# WSN_v1.net
KiCad netlist of a schematic drawn in Altium Designer
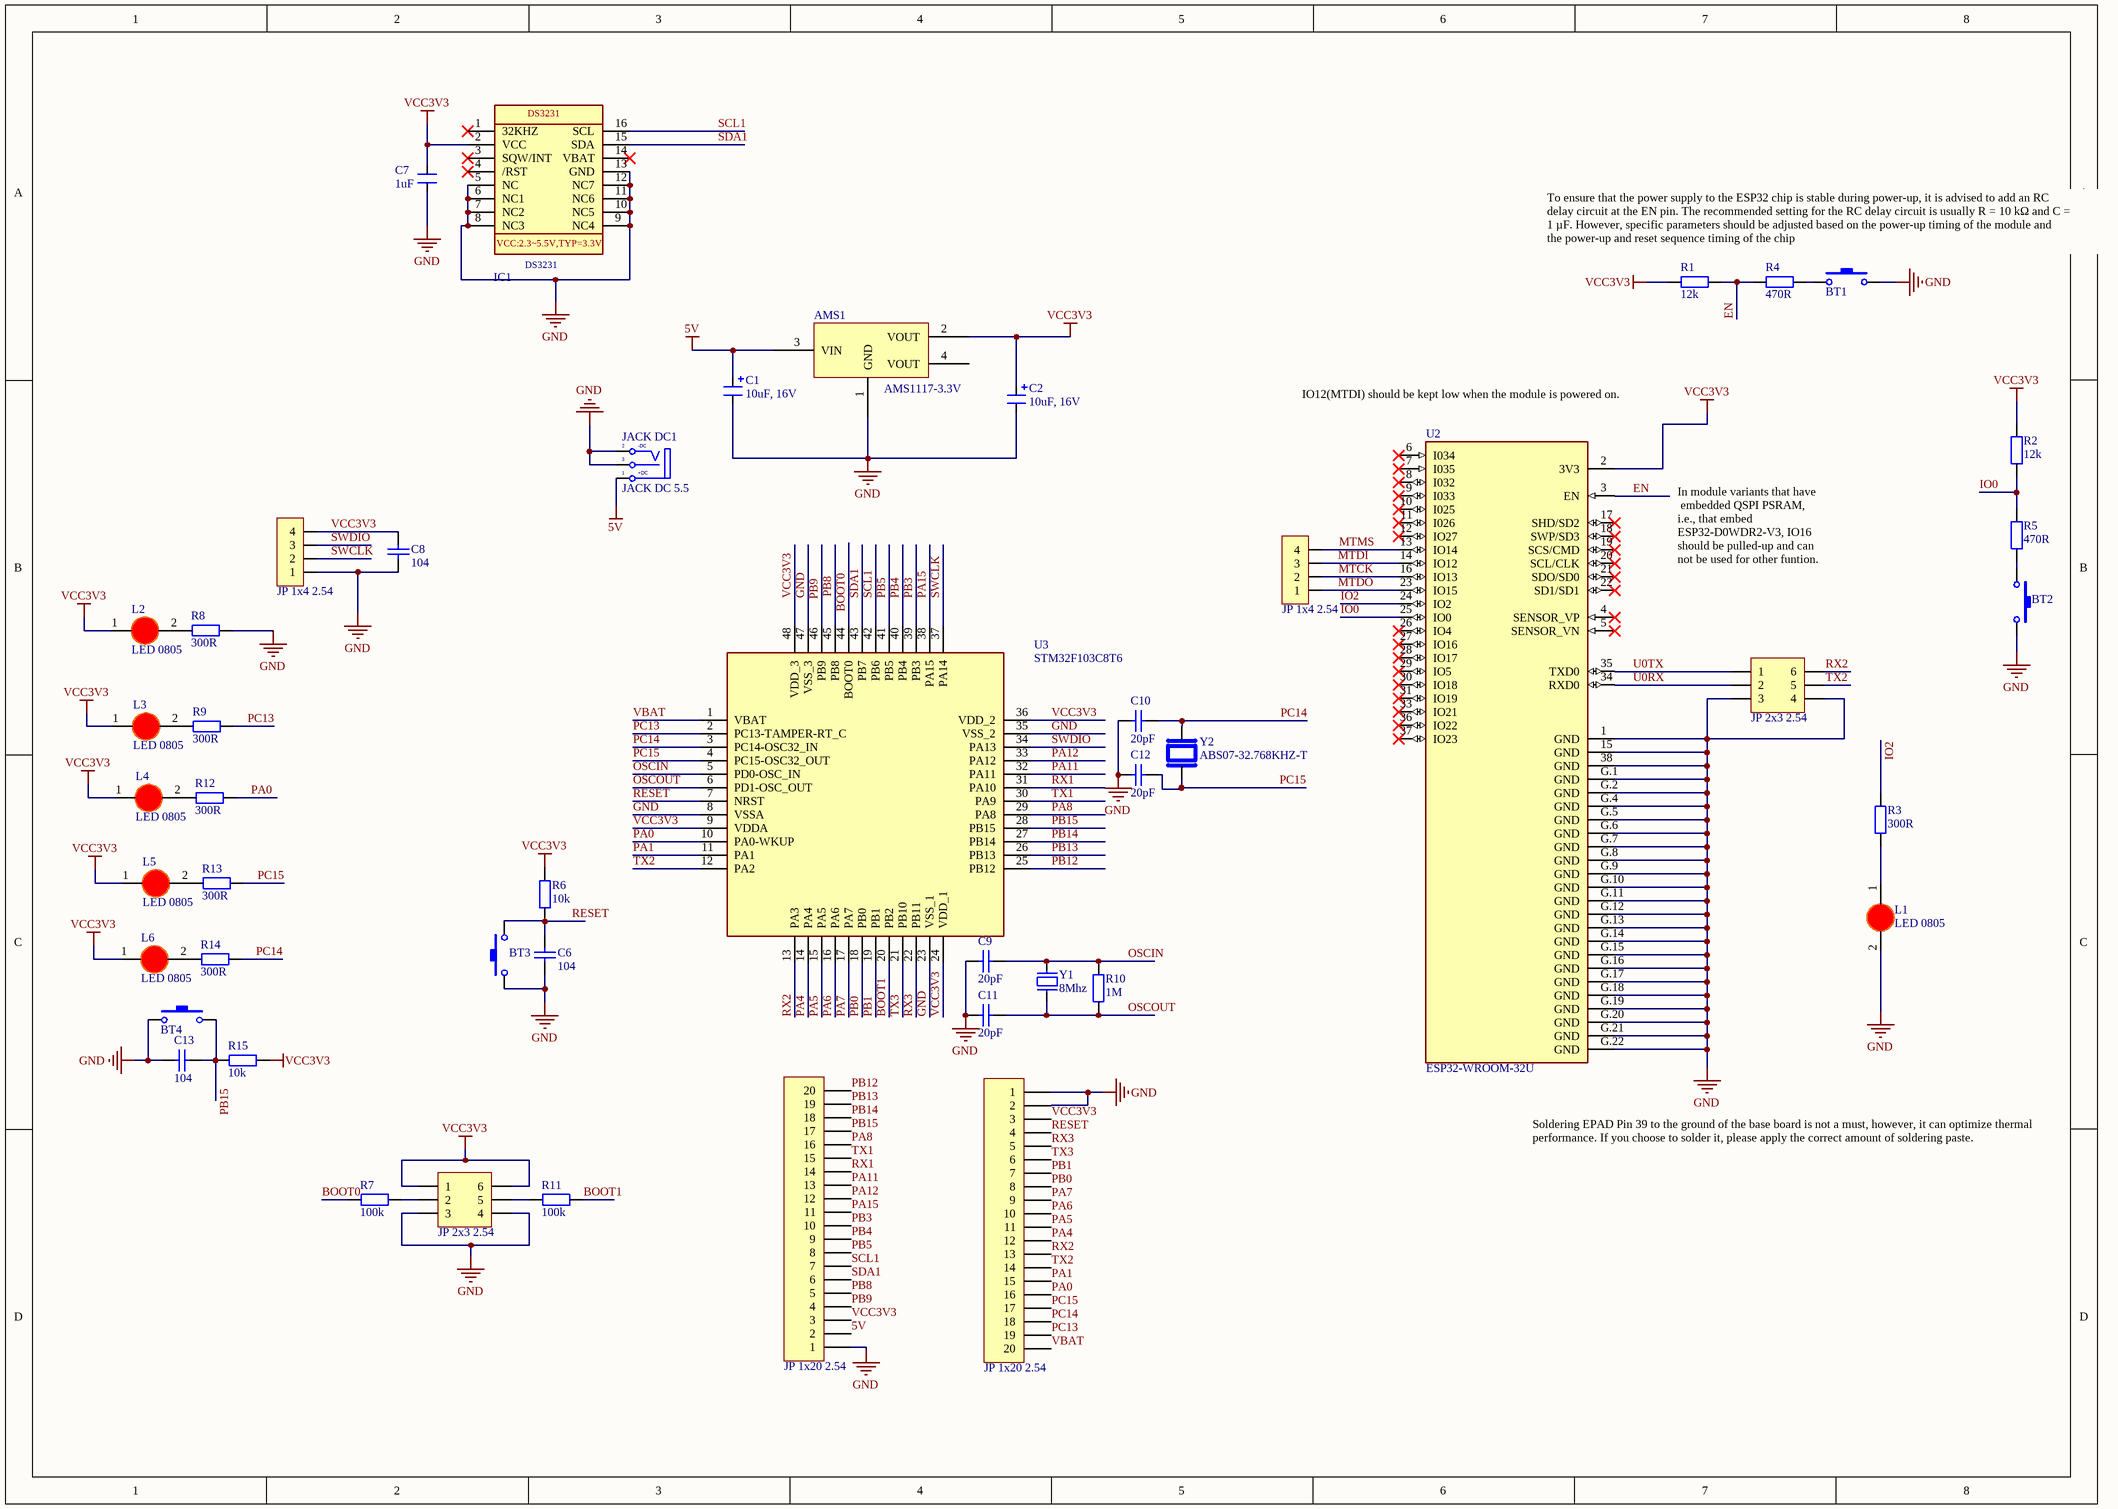
[diagram p0: WSN_v1.SchDoc]

(export (version "E")
  (design (tool "Eeschema 10.0.6"))
  (components
    (comp (ref "AMS1")
      (value "AMS1117-3.3V")
      (footprint "SOT223-4N")
      (description "Dán")
      (libsource (lib "THU VIEN SCH") (part "AMS1117"))
    )
    (comp (ref "BT1")
      (value "Nut Nhan 2 Chan SMD 3x6x2.5")
      (footprint "Nut Nhan 2 Chan SMD 3x6x2.5")
      (libsource (lib "Altium_Lib_by_KhueNguyenCreator") (part "Nut Nhan 2 Chan SMD 3x6x2.5"))
    )
    (comp (ref "BT2")
      (value "Nut Nhan 2 Chan SMD 3x6x2.5")
      (footprint "Nut Nhan 2 Chan SMD 3x6x2.5")
      (libsource (lib "Altium_Lib_by_KhueNguyenCreator") (part "Nut Nhan 2 Chan SMD 3x6x2.5"))
    )
    (comp (ref "BT3")
      (value "Nut Nhan 2 Chan SMD 3x6x2.5")
      (footprint "Nut Nhan 2 Chan SMD 3x6x2.5")
      (libsource (lib "Altium_Lib_by_KhueNguyenCreator") (part "Nut Nhan 2 Chan SMD 3x6x2.5"))
    )
    (comp (ref "BT4")
      (value "Nut Nhan 2 Chan SMD 3x6x2.5")
      (footprint "Nut Nhan 2 Chan SMD 3x6x2.5")
      (libsource (lib "Altium_Lib_by_KhueNguyenCreator") (part "Nut Nhan 2 Chan SMD 3x6x2.5"))
    )
    (comp (ref "C1")
      (value "10uF, 16V")
      (footprint "C_FC_10UF_16V")
      (description "Cap SMD, TANTALUM")
      (libsource (lib "quangnguyen") (part "CM-TANTALUM"))
    )
    (comp (ref "C2")
      (value "10uF, 16V")
      (footprint "C_FC_10UF_16V")
      (description "Cap SMD, TANTALUM")
      (libsource (lib "quangnguyen") (part "CM-TANTALUM"))
    )
    (comp (ref "C6")
      (value "104")
      (footprint "tu 0805")
      (description "Dán")
      (libsource (lib "DoAn2") (part "Tu 0805 104 50V 10%"))
    )
    (comp (ref "C7")
      (value "1uF")
      (footprint "Cap Ceramic 0805 SMD")
      (description "Cap SMD")
      (libsource (lib "quangnguyen_lib_altium") (part "CM"))
    )
    (comp (ref "C8")
      (value "104")
      (footprint "tu 0805")
      (description "Dán")
      (libsource (lib "DoAn2") (part "Tu 0805 104 50V 10%"))
    )
    (comp (ref "C9")
      (value "20pF")
      (footprint "tu 0805")
      (description "Dán")
      (libsource (lib "DoAn2") (part "Tu 0805 20pF 50V 10%"))
    )
    (comp (ref "C10")
      (value "20pF")
      (footprint "tu 0805")
      (description "Dán")
      (libsource (lib "DoAn2") (part "Tu 0805 20pF 50V 10%"))
    )
    (comp (ref "C11")
      (value "20pF")
      (footprint "tu 0805")
      (description "Dán")
      (libsource (lib "DoAn2") (part "Tu 0805 20pF 50V 10%"))
    )
    (comp (ref "C12")
      (value "20pF")
      (footprint "tu 0805")
      (description "Dán")
      (libsource (lib "DoAn2") (part "Tu 0805 20pF 50V 10%"))
    )
    (comp (ref "C13")
      (value "104")
      (footprint "tu 0805")
      (description "Dán")
      (libsource (lib "DoAn2") (part "Tu 0805 104 50V 10%"))
    )
    (comp (ref "IC1")
      (value "DS3231")
      (footprint "SOIC-16")
      (description "RTC DS3231")
      (fields (field (name "MF") "Maxim Integrated"))
      (libsource (lib "Board1") (part "DS3231"))
    )
    (comp (ref "JACK DC1")
      (value "JACK DC 5.5")
      (footprint "JACK DC 5.5")
      (libsource (lib "Altium_Lib_by_KhueNguyenCreator") (part "JACK DC 5.5"))
    )
    (comp (ref "JP1")
      (value "JP 1x4 2.54")
      (footprint "JP 1x4 DT")
      (description "Cắm")
      (libsource (lib "Altium_Lib_by_KhueNguyenCreator") (part "JP 1x4 2.54 Duc Thang"))
    )
    (comp (ref "JP2")
      (value "JP 2x3 2.54")
      (footprint "JP 2x3 DT")
      (description "Cắm")
      (libsource (lib "Altium_Lib_by_KhueNguyenCreator") (part "JP 2x3 2.54 Duc Thang"))
    )
    (comp (ref "JP3")
      (value "JP 1x20 2.54")
      (footprint "JP 1x20 DT")
      (description "Cắm")
      (libsource (lib "Altium_Lib_by_KhueNguyenCreator") (part "JP 1x20 2.54 Duc Thang"))
    )
    (comp (ref "JP4")
      (value "JP 1x20 2.54")
      (footprint "JP 1x20 DT")
      (description "Cắm")
      (libsource (lib "") (part "JP 1x20 2.54 Duc Thang_1"))
    )
    (comp (ref "JP5")
      (value "JP 2x3 2.54")
      (footprint "JP 2x3 DT")
      (description "Cắm")
      (libsource (lib "Altium_Lib_by_KhueNguyenCreator") (part "JP 2x3 2.54 Duc Thang"))
    )
    (comp (ref "JP6")
      (value "JP 1x4 2.54")
      (footprint "JP 1x4 CT")
      (description "Cắm")
      (libsource (lib "Altium_Lib_by_KhueNguyenCreator") (part "JP 1x4 2.54 Cai Thang"))
    )
    (comp (ref "L1")
      (value "LED 0805")
      (footprint "LED-1206-Red")
      (description "Dán")
      (libsource (lib "DoAn2") (part "LED 1206 Do"))
    )
    (comp (ref "L2")
      (value "LED 0805")
      (footprint "LED-1206-Red")
      (description "Dán")
      (libsource (lib "DoAn2") (part "LED 1206 Do"))
    )
    (comp (ref "L3")
      (value "LED 0805")
      (footprint "LED-1206-Red")
      (description "Dán")
      (libsource (lib "DoAn2") (part "LED 1206 Do"))
    )
    (comp (ref "L4")
      (value "LED 0805")
      (footprint "LED-1206-Red")
      (description "Dán")
      (libsource (lib "DoAn2") (part "LED 1206 Do"))
    )
    (comp (ref "L5")
      (value "LED 0805")
      (footprint "LED-1206-Red")
      (description "Dán")
      (libsource (lib "DoAn2") (part "LED 1206 Do"))
    )
    (comp (ref "L6")
      (value "LED 0805")
      (footprint "LED-1206-Red")
      (description "Dán")
      (libsource (lib "DoAn2") (part "LED 1206 Do"))
    )
    (comp (ref "R1")
      (value "12k")
      (footprint "tro smd 0805")
      (description "Dán")
      (libsource (lib "Altium_Lib_by_KhueNguyenCreator") (part "Tro 0805 1% 12k"))
    )
    (comp (ref "R2")
      (value "12k")
      (footprint "tro smd 0805")
      (description "Dán")
      (libsource (lib "Altium_Lib_by_KhueNguyenCreator") (part "Tro 0805 1% 12k"))
    )
    (comp (ref "R3")
      (value "300R")
      (footprint "Tro SMD 0805")
      (description "Dán")
      (libsource (lib "DoAn2") (part "Tro 0805 5% 300R"))
    )
    (comp (ref "R4")
      (value "470R")
      (footprint "Tro SMD 0805")
      (description "Dán")
      (libsource (lib "Altium_Lib_by_KhueNguyenCreator") (part "Tro 0805 5% 470R"))
    )
    (comp (ref "R5")
      (value "470R")
      (footprint "Tro SMD 0805")
      (description "Dán")
      (libsource (lib "") (part "Tro 0805 5% 470R_1"))
    )
    (comp (ref "R6")
      (value "10k")
      (footprint "tro smd 0805")
      (description "Dán")
      (libsource (lib "DoAn2") (part "Tro 0805 5% 10k"))
    )
    (comp (ref "R7")
      (value "100k")
      (footprint "tro smd 0805")
      (description "Dán")
      (libsource (lib "Altium_Lib_by_KhueNguyenCreator") (part "Tro 0805 5% 100k"))
    )
    (comp (ref "R8")
      (value "300R")
      (footprint "Tro SMD 0805")
      (description "Dán")
      (libsource (lib "DoAn2") (part "Tro 0805 5% 300R"))
    )
    (comp (ref "R9")
      (value "300R")
      (footprint "Tro SMD 0805")
      (description "Dán")
      (libsource (lib "DoAn2") (part "Tro 0805 5% 300R"))
    )
    (comp (ref "R10")
      (value "1M")
      (footprint "tro smd 0805")
      (description "Dán")
      (libsource (lib "DoAn2") (part "Tro 0805 5% 1M"))
    )
    (comp (ref "R11")
      (value "100k")
      (footprint "tro smd 0805")
      (description "Dán")
      (libsource (lib "Altium_Lib_by_KhueNguyenCreator") (part "Tro 0805 5% 100k"))
    )
    (comp (ref "R12")
      (value "300R")
      (footprint "Tro SMD 0805")
      (description "Dán")
      (libsource (lib "DoAn2") (part "Tro 0805 5% 300R"))
    )
    (comp (ref "R13")
      (value "300R")
      (footprint "Tro SMD 0805")
      (description "Dán")
      (libsource (lib "DoAn2") (part "Tro 0805 5% 300R"))
    )
    (comp (ref "R14")
      (value "300R")
      (footprint "Tro SMD 0805")
      (description "Dán")
      (libsource (lib "DoAn2") (part "Tro 0805 5% 300R"))
    )
    (comp (ref "R15")
      (value "10k")
      (footprint "tro smd 0805")
      (description "Dán")
      (libsource (lib "DoAn2") (part "Tro 0805 5% 10k"))
    )
    (comp (ref "U2")
      (value "ESP32-WROOM-32U")
      (footprint "XCVR_ESP32-WROOM-32U")
      (fields (field (name "MF") "Espressif Systems"))
      (libsource (lib "ESP32-WROOM-32U") (part "ESP32-WROOM-32U"))
    )
    (comp (ref "U3")
      (value "STM32F103C8T6")
      (footprint "LQFP-48_19.6_393_58X11_SMD")
      (description "ARM® Cortex®-M3 STM32F1 Microcontroller IC 32-Bit 72MHz 64KB (64K x 8) FLASH 48-LQFP (7x7)")
      (fields (field (name "MANUFACTURER") "STMicroelectronics"))
      (libsource (lib "DoAn2") (part "IC_STM32F103C8T6"))
    )
    (comp (ref "Y1")
      (value "8Mhz")
      (footprint "Thach Anh 2 chan SMD")
      (description "Crystal For all Crystal 2pin.")
      (libsource (lib "DoAn2") (part "Thach Anh 2 chan SMD"))
    )
    (comp (ref "Y2")
      (value "ABS07-32.768KHZ-T")
      (footprint "XTAL_ABS07-32.768KHZ-T")
      (description "32.768 kHz Â±20ppm Crystal 12.5pF 70 kOhms 2-SMD, No Lead")
      (fields (field (name "MF") "Abracon"))
      (libsource (lib "ABS07-32.768KHZ-T") (part "ABS07-32.768KHZ-T"))
    )
  )
  (nets
    (net (code "1") (name "/BOOT0") (class "Default")
      (node (ref "R7") (pin "1") (pinfunction "1_1") (pintype "passive"))
      (node (ref "U3") (pin "44") (pinfunction "BOOT0_44") (pintype "passive"))
    )
    (net (code "2") (name "/BOOT1") (class "Default")
      (node (ref "R11") (pin "2") (pinfunction "2_2") (pintype "passive"))
      (node (ref "U3") (pin "20") (pinfunction "PB2_20") (pintype "passive"))
    )
    (net (code "3") (name "/EN") (class "Default")
      (node (ref "R1") (pin "1") (pinfunction "1_1") (pintype "passive"))
      (node (ref "R4") (pin "2") (pinfunction "2_2") (pintype "passive"))
      (node (ref "U2") (pin "3") (pinfunction "EN_3") (pintype "input"))
    )
    (net (code "4") (name "/IO0") (class "Default")
      (node (ref "R2") (pin "1") (pinfunction "1_1") (pintype "passive"))
      (node (ref "R5") (pin "2") (pinfunction "2_2") (pintype "passive"))
      (node (ref "U2") (pin "25") (pinfunction "IO0_25") (pintype "bidirectional"))
    )
    (net (code "5") (name "/IO2") (class "Default")
      (node (ref "R3") (pin "1") (pinfunction "1_1") (pintype "passive"))
      (node (ref "U2") (pin "24") (pinfunction "IO2_24") (pintype "bidirectional"))
    )
    (net (code "6") (name "/MTCK") (class "Default")
      (node (ref "JP6") (pin "2") (pinfunction "2_2") (pintype "passive"))
      (node (ref "U2") (pin "16") (pinfunction "IO13_16") (pintype "bidirectional"))
    )
    (net (code "7") (name "/MTDI") (class "Default")
      (node (ref "JP6") (pin "3") (pinfunction "3_3") (pintype "passive"))
      (node (ref "U2") (pin "14") (pinfunction "IO12_14") (pintype "bidirectional"))
    )
    (net (code "8") (name "/MTDO") (class "Default")
      (node (ref "JP6") (pin "1") (pinfunction "1_1") (pintype "passive"))
      (node (ref "U2") (pin "23") (pinfunction "IO15_23") (pintype "bidirectional"))
    )
    (net (code "9") (name "/MTMS") (class "Default")
      (node (ref "JP6") (pin "4") (pinfunction "4_4") (pintype "passive"))
      (node (ref "U2") (pin "13") (pinfunction "IO14_13") (pintype "bidirectional"))
    )
    (net (code "10") (name "/OSCIN") (class "Default")
      (node (ref "C9") (pin "1") (pinfunction "1_1") (pintype "passive"))
      (node (ref "R10") (pin "2") (pinfunction "2_2") (pintype "passive"))
      (node (ref "U3") (pin "5") (pinfunction "PD0-OSC_IN_5") (pintype "passive"))
      (node (ref "Y1") (pin "2") (pinfunction "2_2") (pintype "passive"))
    )
    (net (code "11") (name "/OSCOUT") (class "Default")
      (node (ref "C11") (pin "1") (pinfunction "1_1") (pintype "passive"))
      (node (ref "R10") (pin "1") (pinfunction "1_1") (pintype "passive"))
      (node (ref "U3") (pin "6") (pinfunction "PD1-OSC_OUT_6") (pintype "passive"))
      (node (ref "Y1") (pin "1") (pinfunction "1_1") (pintype "passive"))
    )
    (net (code "12") (name "/PA0") (class "Default")
      (node (ref "JP4") (pin "16") (pinfunction "16_16") (pintype "passive"))
      (node (ref "R12") (pin "2") (pinfunction "2_2") (pintype "passive"))
      (node (ref "U3") (pin "10") (pinfunction "PA0-WKUP_10") (pintype "passive"))
    )
    (net (code "13") (name "/PA1") (class "Default")
      (node (ref "JP4") (pin "15") (pinfunction "15_15") (pintype "passive"))
      (node (ref "U3") (pin "11") (pinfunction "PA1_11") (pintype "passive"))
    )
    (net (code "14") (name "/PA4") (class "Default")
      (node (ref "JP4") (pin "12") (pinfunction "12_12") (pintype "passive"))
      (node (ref "U3") (pin "14") (pinfunction "PA4_14") (pintype "passive"))
    )
    (net (code "15") (name "/PA5") (class "Default")
      (node (ref "JP4") (pin "11") (pinfunction "11_11") (pintype "passive"))
      (node (ref "U3") (pin "15") (pinfunction "PA5_15") (pintype "passive"))
    )
    (net (code "16") (name "/PA6") (class "Default")
      (node (ref "JP4") (pin "10") (pinfunction "10_10") (pintype "passive"))
      (node (ref "U3") (pin "16") (pinfunction "PA6_16") (pintype "passive"))
    )
    (net (code "17") (name "/PA7") (class "Default")
      (node (ref "JP4") (pin "9") (pinfunction "9_9") (pintype "passive"))
      (node (ref "U3") (pin "17") (pinfunction "PA7_17") (pintype "passive"))
    )
    (net (code "18") (name "/PA8") (class "Default")
      (node (ref "JP3") (pin "16") (pinfunction "16_16") (pintype "passive"))
      (node (ref "U3") (pin "29") (pinfunction "PA8_29") (pintype "passive"))
    )
    (net (code "19") (name "/PA11") (class "Default")
      (node (ref "JP3") (pin "13") (pinfunction "13_13") (pintype "passive"))
      (node (ref "U3") (pin "32") (pinfunction "PA11_32") (pintype "passive"))
    )
    (net (code "20") (name "/PA12") (class "Default")
      (node (ref "JP3") (pin "12") (pinfunction "12_12") (pintype "passive"))
      (node (ref "U3") (pin "33") (pinfunction "PA12_33") (pintype "passive"))
    )
    (net (code "21") (name "/PA15") (class "Default")
      (node (ref "JP3") (pin "11") (pinfunction "11_11") (pintype "passive"))
      (node (ref "U3") (pin "38") (pinfunction "PA15_38") (pintype "passive"))
    )
    (net (code "22") (name "/PB0") (class "Default")
      (node (ref "JP4") (pin "8") (pinfunction "8_8") (pintype "passive"))
      (node (ref "U3") (pin "18") (pinfunction "PB0_18") (pintype "passive"))
    )
    (net (code "23") (name "/PB1") (class "Default")
      (node (ref "JP4") (pin "7") (pinfunction "7_7") (pintype "passive"))
      (node (ref "U3") (pin "19") (pinfunction "PB1_19") (pintype "passive"))
    )
    (net (code "24") (name "/PB3") (class "Default")
      (node (ref "JP3") (pin "10") (pinfunction "10_10") (pintype "passive"))
      (node (ref "U3") (pin "39") (pinfunction "PB3_39") (pintype "passive"))
    )
    (net (code "25") (name "/PB4") (class "Default")
      (node (ref "JP3") (pin "9") (pinfunction "9_9") (pintype "passive"))
      (node (ref "U3") (pin "40") (pinfunction "PB4_40") (pintype "passive"))
    )
    (net (code "26") (name "/PB5") (class "Default")
      (node (ref "JP3") (pin "8") (pinfunction "8_8") (pintype "passive"))
      (node (ref "U3") (pin "41") (pinfunction "PB5_41") (pintype "passive"))
    )
    (net (code "27") (name "/PB8") (class "Default")
      (node (ref "JP3") (pin "5") (pinfunction "5_5") (pintype "passive"))
      (node (ref "U3") (pin "45") (pinfunction "PB8_45") (pintype "passive"))
    )
    (net (code "28") (name "/PB9") (class "Default")
      (node (ref "JP3") (pin "4") (pinfunction "4_4") (pintype "passive"))
      (node (ref "U3") (pin "46") (pinfunction "PB9_46") (pintype "passive"))
    )
    (net (code "29") (name "/PB12") (class "Default")
      (node (ref "JP3") (pin "20") (pinfunction "20_20") (pintype "passive"))
      (node (ref "U3") (pin "25") (pinfunction "PB12_25") (pintype "passive"))
    )
    (net (code "30") (name "/PB13") (class "Default")
      (node (ref "JP3") (pin "19") (pinfunction "19_19") (pintype "passive"))
      (node (ref "U3") (pin "26") (pinfunction "PB13_26") (pintype "passive"))
    )
    (net (code "31") (name "/PB14") (class "Default")
      (node (ref "JP3") (pin "18") (pinfunction "18_18") (pintype "passive"))
      (node (ref "U3") (pin "27") (pinfunction "PB14_27") (pintype "passive"))
    )
    (net (code "32") (name "/PB15") (class "Default")
      (node (ref "BT4") (pin "2") (pinfunction "2_2") (pintype "passive"))
      (node (ref "C13") (pin "1") (pinfunction "1_1") (pintype "passive"))
      (node (ref "JP3") (pin "17") (pinfunction "17_17") (pintype "passive"))
      (node (ref "R15") (pin "1") (pinfunction "1_1") (pintype "passive"))
      (node (ref "U3") (pin "28") (pinfunction "PB15_28") (pintype "passive"))
    )
    (net (code "33") (name "/PC13") (class "Default")
      (node (ref "JP4") (pin "19") (pinfunction "19_19") (pintype "passive"))
      (node (ref "R9") (pin "2") (pinfunction "2_2") (pintype "passive"))
      (node (ref "U3") (pin "2") (pinfunction "PC13-TAMPER-RT_C_2") (pintype "passive"))
    )
    (net (code "34") (name "/PC14") (class "Default")
      (node (ref "C10") (pin "1") (pinfunction "1_1") (pintype "passive"))
      (node (ref "JP4") (pin "18") (pinfunction "18_18") (pintype "passive"))
      (node (ref "R14") (pin "2") (pinfunction "2_2") (pintype "passive"))
      (node (ref "U3") (pin "3") (pinfunction "PC14-OSC32_IN_3") (pintype "passive"))
      (node (ref "Y2") (pin "2") (pinfunction "2_2") (pintype "passive"))
    )
    (net (code "35") (name "/PC15") (class "Default")
      (node (ref "C12") (pin "1") (pinfunction "1_1") (pintype "passive"))
      (node (ref "JP4") (pin "17") (pinfunction "17_17") (pintype "passive"))
      (node (ref "R13") (pin "2") (pinfunction "2_2") (pintype "passive"))
      (node (ref "U3") (pin "4") (pinfunction "PC15-OSC32_OUT_4") (pintype "passive"))
      (node (ref "Y2") (pin "1") (pinfunction "1_1") (pintype "passive"))
    )
    (net (code "36") (name "/RESET") (class "Default")
      (node (ref "BT3") (pin "2") (pinfunction "2_2") (pintype "passive"))
      (node (ref "C6") (pin "1") (pinfunction "1_1") (pintype "passive"))
      (node (ref "JP4") (pin "4") (pinfunction "4_4") (pintype "passive"))
      (node (ref "R6") (pin "1") (pinfunction "1_1") (pintype "passive"))
      (node (ref "U3") (pin "7") (pinfunction "NRST_7") (pintype "passive"))
    )
    (net (code "37") (name "/RX1") (class "Default")
      (node (ref "JP3") (pin "14") (pinfunction "14_14") (pintype "passive"))
      (node (ref "U3") (pin "31") (pinfunction "PA10_31") (pintype "passive"))
    )
    (net (code "38") (name "/RX2") (class "Default")
      (node (ref "JP4") (pin "13") (pinfunction "13_13") (pintype "passive"))
      (node (ref "JP5") (pin "6") (pinfunction "6_6") (pintype "passive"))
      (node (ref "U3") (pin "13") (pinfunction "PA3_13") (pintype "passive"))
    )
    (net (code "39") (name "/RX3") (class "Default")
      (node (ref "JP4") (pin "5") (pinfunction "5_5") (pintype "passive"))
      (node (ref "U3") (pin "22") (pinfunction "PB11_22") (pintype "passive"))
    )
    (net (code "40") (name "/SCL1") (class "Default")
      (node (ref "IC1") (pin "16") (pinfunction "SCL_16") (pintype "passive"))
      (node (ref "JP3") (pin "7") (pinfunction "7_7") (pintype "passive"))
      (node (ref "U3") (pin "42") (pinfunction "PB6_42") (pintype "passive"))
    )
    (net (code "41") (name "/SDA1") (class "Default")
      (node (ref "IC1") (pin "15") (pinfunction "SDA_15") (pintype "passive"))
      (node (ref "JP3") (pin "6") (pinfunction "6_6") (pintype "passive"))
      (node (ref "U3") (pin "43") (pinfunction "PB7_43") (pintype "passive"))
    )
    (net (code "42") (name "/SWCLK") (class "Default")
      (node (ref "JP1") (pin "2") (pinfunction "2_2") (pintype "passive"))
      (node (ref "U3") (pin "37") (pinfunction "PA14_37") (pintype "passive"))
    )
    (net (code "43") (name "/SWDIO") (class "Default")
      (node (ref "JP1") (pin "3") (pinfunction "3_3") (pintype "passive"))
      (node (ref "U3") (pin "34") (pinfunction "PA13_34") (pintype "passive"))
    )
    (net (code "44") (name "/TX1") (class "Default")
      (node (ref "JP3") (pin "15") (pinfunction "15_15") (pintype "passive"))
      (node (ref "U3") (pin "30") (pinfunction "PA9_30") (pintype "passive"))
    )
    (net (code "45") (name "/TX2") (class "Default")
      (node (ref "JP4") (pin "14") (pinfunction "14_14") (pintype "passive"))
      (node (ref "JP5") (pin "5") (pinfunction "5_5") (pintype "passive"))
      (node (ref "U3") (pin "12") (pinfunction "PA2_12") (pintype "passive"))
    )
    (net (code "46") (name "/TX3") (class "Default")
      (node (ref "JP4") (pin "6") (pinfunction "6_6") (pintype "passive"))
      (node (ref "U3") (pin "21") (pinfunction "PB10_21") (pintype "passive"))
    )
    (net (code "47") (name "/U0RX") (class "Default")
      (node (ref "JP5") (pin "2") (pinfunction "2_2") (pintype "passive"))
      (node (ref "U2") (pin "34") (pinfunction "RXD0_34") (pintype "bidirectional"))
    )
    (net (code "48") (name "/U0TX") (class "Default")
      (node (ref "JP5") (pin "1") (pinfunction "1_1") (pintype "passive"))
      (node (ref "U2") (pin "35") (pinfunction "TXD0_35") (pintype "bidirectional"))
    )
    (net (code "49") (name "/VBAT") (class "Default")
      (node (ref "JP4") (pin "20") (pinfunction "20_20") (pintype "passive"))
      (node (ref "U3") (pin "1") (pinfunction "VBAT_1") (pintype "passive"))
    )
    (net (code "50") (name "5V") (class "Default")
      (node (ref "AMS1") (pin "3") (pinfunction "VIN_3") (pintype "passive"))
      (node (ref "C1") (pin "1") (pinfunction "1_1") (pintype "passive"))
      (node (ref "JACK DC1") (pin "1") (pinfunction "T_1") (pintype "passive"))
      (node (ref "JP3") (pin "2") (pinfunction "2_2") (pintype "passive"))
    )
    (net (code "51") (name "GND") (class "Default")
      (node (ref "AMS1") (pin "1") (pinfunction "GND_1") (pintype "passive"))
      (node (ref "BT1") (pin "2") (pinfunction "2_2") (pintype "passive"))
      (node (ref "BT2") (pin "2") (pinfunction "2_2") (pintype "passive"))
      (node (ref "BT3") (pin "1") (pinfunction "1_1") (pintype "passive"))
      (node (ref "BT4") (pin "1") (pinfunction "1_1") (pintype "passive"))
      (node (ref "C1") (pin "2") (pinfunction "2_2") (pintype "passive"))
      (node (ref "C10") (pin "2") (pinfunction "2_2") (pintype "passive"))
      (node (ref "C11") (pin "2") (pinfunction "2_2") (pintype "passive"))
      (node (ref "C12") (pin "2") (pinfunction "2_2") (pintype "passive"))
      (node (ref "C13") (pin "2") (pinfunction "2_2") (pintype "passive"))
      (node (ref "C2") (pin "2") (pinfunction "2_2") (pintype "passive"))
      (node (ref "C6") (pin "2") (pinfunction "2_2") (pintype "passive"))
      (node (ref "C7") (pin "1") (pinfunction "1_1") (pintype "passive"))
      (node (ref "C8") (pin "2") (pinfunction "2_2") (pintype "passive"))
      (node (ref "C9") (pin "2") (pinfunction "2_2") (pintype "passive"))
      (node (ref "IC1") (pin "10") (pinfunction "NC5_10") (pintype "passive"))
      (node (ref "IC1") (pin "11") (pinfunction "NC6_11") (pintype "passive"))
      (node (ref "IC1") (pin "12") (pinfunction "NC7_12") (pintype "passive"))
      (node (ref "IC1") (pin "13") (pinfunction "GND_13") (pintype "power_in"))
      (node (ref "IC1") (pin "5") (pinfunction "NC_5") (pintype "passive"))
      (node (ref "IC1") (pin "6") (pinfunction "NC1_6") (pintype "passive"))
      (node (ref "IC1") (pin "7") (pinfunction "NC2_7") (pintype "passive"))
      (node (ref "IC1") (pin "8") (pinfunction "NC3_8") (pintype "passive"))
      (node (ref "IC1") (pin "9") (pinfunction "NC4_9") (pintype "passive"))
      (node (ref "JACK DC1") (pin "2") (pinfunction "TN_2") (pintype "passive"))
      (node (ref "JACK DC1") (pin "3") (pinfunction "S_3") (pintype "power_in"))
      (node (ref "JP1") (pin "1") (pinfunction "1_1") (pintype "passive"))
      (node (ref "JP2") (pin "3") (pinfunction "3_3") (pintype "passive"))
      (node (ref "JP2") (pin "4") (pinfunction "4_4") (pintype "passive"))
      (node (ref "JP3") (pin "1") (pinfunction "1_1") (pintype "passive"))
      (node (ref "JP4") (pin "1") (pinfunction "1_1") (pintype "passive"))
      (node (ref "JP4") (pin "2") (pinfunction "2_2") (pintype "passive"))
      (node (ref "JP5") (pin "3") (pinfunction "3_3") (pintype "passive"))
      (node (ref "JP5") (pin "4") (pinfunction "4_4") (pintype "passive"))
      (node (ref "L1") (pin "2") (pinfunction "K_2") (pintype "passive"))
      (node (ref "R8") (pin "2") (pinfunction "2_2") (pintype "passive"))
      (node (ref "U2") (pin "1") (pinfunction "GND_1") (pintype "power_in"))
      (node (ref "U2") (pin "15") (pinfunction "GND_15") (pintype "power_in"))
      (node (ref "U2") (pin "38") (pinfunction "GND_38") (pintype "power_in"))
      (node (ref "U2") (pin "G.1") (pinfunction "GND_G.1") (pintype "power_in"))
      (node (ref "U2") (pin "G.10") (pinfunction "GND_G.10") (pintype "power_in"))
      (node (ref "U2") (pin "G.11") (pinfunction "GND_G.11") (pintype "power_in"))
      (node (ref "U2") (pin "G.12") (pinfunction "GND_G.12") (pintype "power_in"))
      (node (ref "U2") (pin "G.13") (pinfunction "GND_G.13") (pintype "power_in"))
      (node (ref "U2") (pin "G.14") (pinfunction "GND_G.14") (pintype "power_in"))
      (node (ref "U2") (pin "G.15") (pinfunction "GND_G.15") (pintype "power_in"))
      (node (ref "U2") (pin "G.16") (pinfunction "GND_G.16") (pintype "power_in"))
      (node (ref "U2") (pin "G.17") (pinfunction "GND_G.17") (pintype "power_in"))
      (node (ref "U2") (pin "G.18") (pinfunction "GND_G.18") (pintype "power_in"))
      (node (ref "U2") (pin "G.19") (pinfunction "GND_G.19") (pintype "power_in"))
      (node (ref "U2") (pin "G.2") (pinfunction "GND_G.2") (pintype "power_in"))
      (node (ref "U2") (pin "G.20") (pinfunction "GND_G.20") (pintype "power_in"))
      (node (ref "U2") (pin "G.21") (pinfunction "GND_G.21") (pintype "power_in"))
      (node (ref "U2") (pin "G.22") (pinfunction "GND_G.22") (pintype "power_in"))
      (node (ref "U2") (pin "G.4") (pinfunction "GND_G.4") (pintype "power_in"))
      (node (ref "U2") (pin "G.5") (pinfunction "GND_G.5") (pintype "power_in"))
      (node (ref "U2") (pin "G.6") (pinfunction "GND_G.6") (pintype "power_in"))
      (node (ref "U2") (pin "G.7") (pinfunction "GND_G.7") (pintype "power_in"))
      (node (ref "U2") (pin "G.8") (pinfunction "GND_G.8") (pintype "power_in"))
      (node (ref "U2") (pin "G.9") (pinfunction "GND_G.9") (pintype "power_in"))
      (node (ref "U3") (pin "23") (pinfunction "VSS_1_23") (pintype "passive"))
      (node (ref "U3") (pin "35") (pinfunction "VSS_2_35") (pintype "passive"))
      (node (ref "U3") (pin "47") (pinfunction "VSS_3_47") (pintype "passive"))
      (node (ref "U3") (pin "8") (pinfunction "VSSA_8") (pintype "passive"))
    )
    (net (code "52") (name "Net-(BT1-Pad1)") (class "Default")
      (node (ref "BT1") (pin "1") (pinfunction "1_1") (pintype "passive"))
      (node (ref "R4") (pin "1") (pinfunction "1_1") (pintype "passive"))
    )
    (net (code "53") (name "Net-(BT2-Pad1)") (class "Default")
      (node (ref "BT2") (pin "1") (pinfunction "1_1") (pintype "passive"))
      (node (ref "R5") (pin "1") (pinfunction "1_1") (pintype "passive"))
    )
    (net (code "54") (name "Net-(JP2-Pad2)") (class "Default")
      (node (ref "JP2") (pin "2") (pinfunction "2_2") (pintype "passive"))
      (node (ref "R7") (pin "2") (pinfunction "2_2") (pintype "passive"))
    )
    (net (code "55") (name "Net-(JP2-Pad5)") (class "Default")
      (node (ref "JP2") (pin "5") (pinfunction "5_5") (pintype "passive"))
      (node (ref "R11") (pin "1") (pinfunction "1_1") (pintype "passive"))
    )
    (net (code "56") (name "Net-(L1-A)") (class "Default")
      (node (ref "L1") (pin "1") (pinfunction "A_1") (pintype "passive"))
      (node (ref "R3") (pin "2") (pinfunction "2_2") (pintype "passive"))
    )
    (net (code "57") (name "Net-(L2-K)") (class "Default")
      (node (ref "L2") (pin "2") (pinfunction "K_2") (pintype "passive"))
      (node (ref "R8") (pin "1") (pinfunction "1_1") (pintype "passive"))
    )
    (net (code "58") (name "Net-(L3-K)") (class "Default")
      (node (ref "L3") (pin "2") (pinfunction "K_2") (pintype "passive"))
      (node (ref "R9") (pin "1") (pinfunction "1_1") (pintype "passive"))
    )
    (net (code "59") (name "Net-(L4-K)") (class "Default")
      (node (ref "L4") (pin "2") (pinfunction "K_2") (pintype "passive"))
      (node (ref "R12") (pin "1") (pinfunction "1_1") (pintype "passive"))
    )
    (net (code "60") (name "Net-(L5-K)") (class "Default")
      (node (ref "L5") (pin "2") (pinfunction "K_2") (pintype "passive"))
      (node (ref "R13") (pin "1") (pinfunction "1_1") (pintype "passive"))
    )
    (net (code "61") (name "Net-(L6-K)") (class "Default")
      (node (ref "L6") (pin "2") (pinfunction "K_2") (pintype "passive"))
      (node (ref "R14") (pin "1") (pinfunction "1_1") (pintype "passive"))
    )
    (net (code "62") (name "VCC3V3") (class "Default")
      (node (ref "AMS1") (pin "2") (pinfunction "VOUT_2") (pintype "passive"))
      (node (ref "C2") (pin "1") (pinfunction "1_1") (pintype "passive"))
      (node (ref "C7") (pin "2") (pinfunction "2_2") (pintype "passive"))
      (node (ref "C8") (pin "1") (pinfunction "1_1") (pintype "passive"))
      (node (ref "IC1") (pin "2") (pinfunction "VCC_2") (pintype "power_in"))
      (node (ref "JP1") (pin "4") (pinfunction "4_4") (pintype "passive"))
      (node (ref "JP2") (pin "1") (pinfunction "1_1") (pintype "passive"))
      (node (ref "JP2") (pin "6") (pinfunction "6_6") (pintype "passive"))
      (node (ref "JP3") (pin "3") (pinfunction "3_3") (pintype "passive"))
      (node (ref "JP4") (pin "3") (pinfunction "3_3") (pintype "passive"))
      (node (ref "L2") (pin "1") (pinfunction "A_1") (pintype "passive"))
      (node (ref "L3") (pin "1") (pinfunction "A_1") (pintype "passive"))
      (node (ref "L4") (pin "1") (pinfunction "A_1") (pintype "passive"))
      (node (ref "L5") (pin "1") (pinfunction "A_1") (pintype "passive"))
      (node (ref "L6") (pin "1") (pinfunction "A_1") (pintype "passive"))
      (node (ref "R1") (pin "2") (pinfunction "2_2") (pintype "passive"))
      (node (ref "R15") (pin "2") (pinfunction "2_2") (pintype "passive"))
      (node (ref "R2") (pin "2") (pinfunction "2_2") (pintype "passive"))
      (node (ref "R6") (pin "2") (pinfunction "2_2") (pintype "passive"))
      (node (ref "U2") (pin "2") (pinfunction "3V3_2") (pintype "power_in"))
      (node (ref "U3") (pin "24") (pinfunction "VDD_1_24") (pintype "passive"))
      (node (ref "U3") (pin "36") (pinfunction "VDD_2_36") (pintype "passive"))
      (node (ref "U3") (pin "48") (pinfunction "VDD_3_48") (pintype "passive"))
      (node (ref "U3") (pin "9") (pinfunction "VDDA_9") (pintype "passive"))
    )
    (net (code "63") (name "unconnected-(AMS1-VOUT-Pad4)") (class "Default")
      (node (ref "AMS1") (pin "4") (pinfunction "VOUT_4") (pintype "passive"))
    )
    (net (code "64") (name "unconnected-(IC1-32KHZ-Pad1)") (class "Default")
      (node (ref "IC1") (pin "1") (pinfunction "32KHZ_1") (pintype "passive+no_connect"))
    )
    (net (code "65") (name "unconnected-(IC1-SQW{slash}INT-Pad3)") (class "Default")
      (node (ref "IC1") (pin "3") (pinfunction "SQW/INT_3") (pintype "passive+no_connect"))
    )
    (net (code "66") (name "unconnected-(IC1-VBAT-Pad14)") (class "Default")
      (node (ref "IC1") (pin "14") (pinfunction "VBAT_14") (pintype "power_in+no_connect"))
    )
    (net (code "67") (name "unconnected-(IC1-{slash}RST-Pad4)") (class "Default")
      (node (ref "IC1") (pin "4") (pinfunction "/RST_4") (pintype "passive+no_connect"))
    )
    (net (code "68") (name "unconnected-(U2-I025-Pad10)") (class "Default")
      (node (ref "U2") (pin "10") (pinfunction "I025_10") (pintype "bidirectional+no_connect"))
    )
    (net (code "69") (name "unconnected-(U2-I026-Pad11)") (class "Default")
      (node (ref "U2") (pin "11") (pinfunction "I026_11") (pintype "bidirectional+no_connect"))
    )
    (net (code "70") (name "unconnected-(U2-I032-Pad8)") (class "Default")
      (node (ref "U2") (pin "8") (pinfunction "I032_8") (pintype "bidirectional+no_connect"))
    )
    (net (code "71") (name "unconnected-(U2-I033-Pad9)") (class "Default")
      (node (ref "U2") (pin "9") (pinfunction "I033_9") (pintype "bidirectional+no_connect"))
    )
    (net (code "72") (name "unconnected-(U2-I034-Pad6)") (class "Default")
      (node (ref "U2") (pin "6") (pinfunction "I034_6") (pintype "input+no_connect"))
    )
    (net (code "73") (name "unconnected-(U2-I035-Pad7)") (class "Default")
      (node (ref "U2") (pin "7") (pinfunction "I035_7") (pintype "input+no_connect"))
    )
    (net (code "74") (name "unconnected-(U2-IO4-Pad26)") (class "Default")
      (node (ref "U2") (pin "26") (pinfunction "IO4_26") (pintype "bidirectional+no_connect"))
    )
    (net (code "75") (name "unconnected-(U2-IO5-Pad29)") (class "Default")
      (node (ref "U2") (pin "29") (pinfunction "IO5_29") (pintype "bidirectional+no_connect"))
    )
    (net (code "76") (name "unconnected-(U2-IO16-Pad27)") (class "Default")
      (node (ref "U2") (pin "27") (pinfunction "IO16_27") (pintype "bidirectional+no_connect"))
    )
    (net (code "77") (name "unconnected-(U2-IO17-Pad28)") (class "Default")
      (node (ref "U2") (pin "28") (pinfunction "IO17_28") (pintype "bidirectional+no_connect"))
    )
    (net (code "78") (name "unconnected-(U2-IO18-Pad30)") (class "Default")
      (node (ref "U2") (pin "30") (pinfunction "IO18_30") (pintype "bidirectional+no_connect"))
    )
    (net (code "79") (name "unconnected-(U2-IO19-Pad31)") (class "Default")
      (node (ref "U2") (pin "31") (pinfunction "IO19_31") (pintype "bidirectional+no_connect"))
    )
    (net (code "80") (name "unconnected-(U2-IO21-Pad33)") (class "Default")
      (node (ref "U2") (pin "33") (pinfunction "IO21_33") (pintype "bidirectional+no_connect"))
    )
    (net (code "81") (name "unconnected-(U2-IO22-Pad36)") (class "Default")
      (node (ref "U2") (pin "36") (pinfunction "IO22_36") (pintype "bidirectional+no_connect"))
    )
    (net (code "82") (name "unconnected-(U2-IO23-Pad37)") (class "Default")
      (node (ref "U2") (pin "37") (pinfunction "IO23_37") (pintype "bidirectional+no_connect"))
    )
    (net (code "83") (name "unconnected-(U2-IO27-Pad12)") (class "Default")
      (node (ref "U2") (pin "12") (pinfunction "IO27_12") (pintype "bidirectional+no_connect"))
    )
    (net (code "84") (name "unconnected-(U2-SCL{slash}CLK-Pad20)") (class "Default")
      (node (ref "U2") (pin "20") (pinfunction "SCL/CLK_20") (pintype "bidirectional+no_connect"))
    )
    (net (code "85") (name "unconnected-(U2-SCS{slash}CMD-Pad19)") (class "Default")
      (node (ref "U2") (pin "19") (pinfunction "SCS/CMD_19") (pintype "bidirectional+no_connect"))
    )
    (net (code "86") (name "unconnected-(U2-SD1{slash}SD1-Pad22)") (class "Default")
      (node (ref "U2") (pin "22") (pinfunction "SD1/SD1_22") (pintype "bidirectional+no_connect"))
    )
    (net (code "87") (name "unconnected-(U2-SDO{slash}SD0-Pad21)") (class "Default")
      (node (ref "U2") (pin "21") (pinfunction "SDO/SD0_21") (pintype "bidirectional+no_connect"))
    )
    (net (code "88") (name "unconnected-(U2-SENSOR_VN-Pad5)") (class "Default")
      (node (ref "U2") (pin "5") (pinfunction "SENSOR_VN_5") (pintype "input+no_connect"))
    )
    (net (code "89") (name "unconnected-(U2-SENSOR_VP-Pad4)") (class "Default")
      (node (ref "U2") (pin "4") (pinfunction "SENSOR_VP_4") (pintype "input+no_connect"))
    )
    (net (code "90") (name "unconnected-(U2-SHD{slash}SD2-Pad17)") (class "Default")
      (node (ref "U2") (pin "17") (pinfunction "SHD/SD2_17") (pintype "bidirectional+no_connect"))
    )
    (net (code "91") (name "unconnected-(U2-SWP{slash}SD3-Pad18)") (class "Default")
      (node (ref "U2") (pin "18") (pinfunction "SWP/SD3_18") (pintype "bidirectional+no_connect"))
    )
  )
)
